# lab5.net
KiCad netlist of a schematic drawn in EAGLE
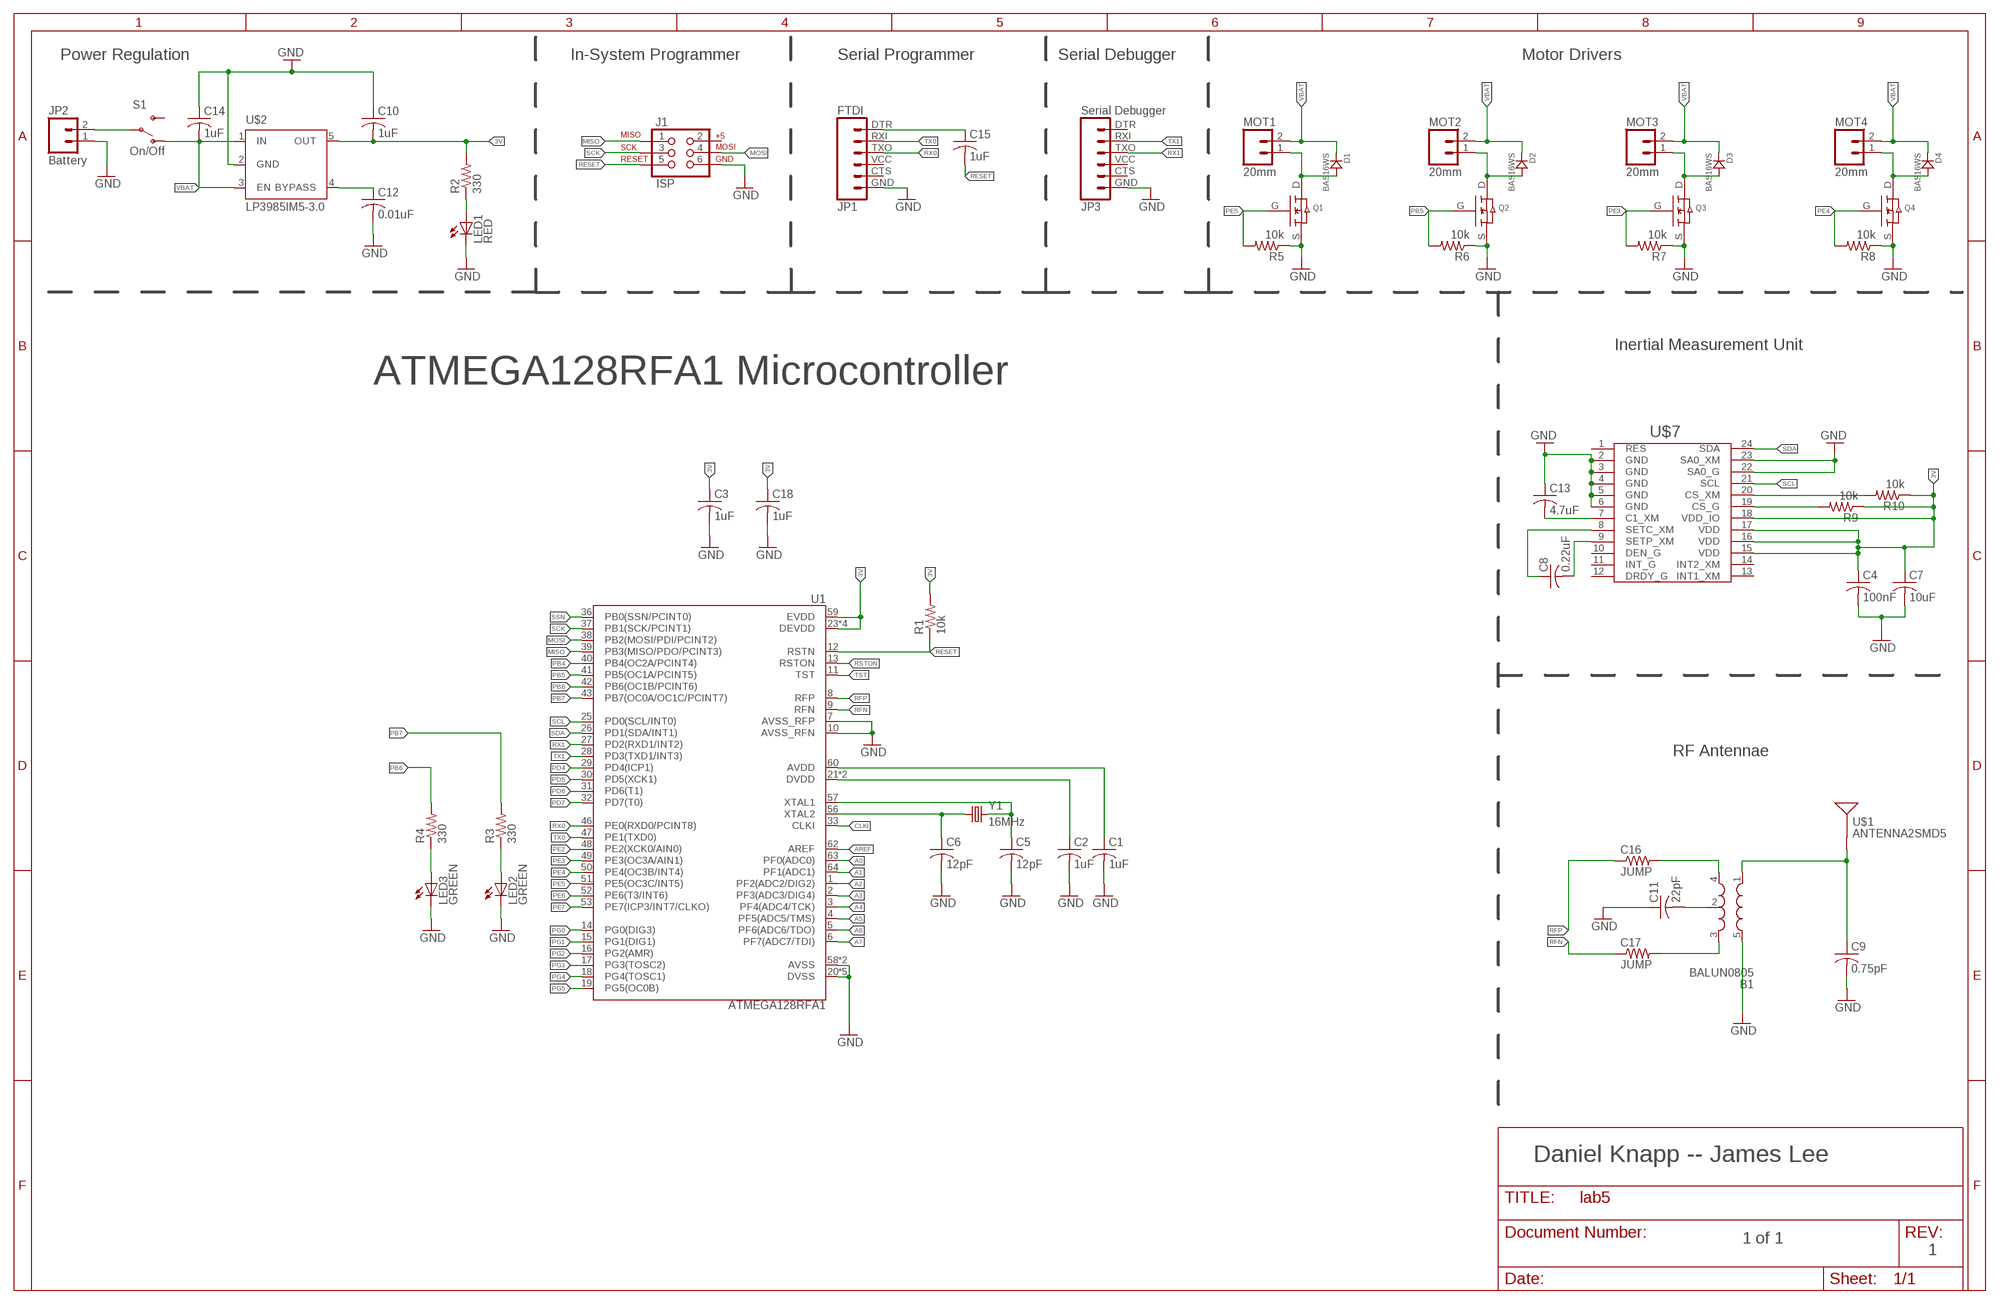
[diagram p0: schematic, sheet 1]

(export (version "E")
  (design (tool "Eeschema 10.0.6"))
  (components
    (comp (ref "B1")
      (value "BALUN0805")
      (footprint "eagle-import:BALUN")
      (libsource (lib "eagle-import") (part "BALUN0805"))
    )
    (comp (ref "C1")
      (value "1uF")
      (footprint "eagle-import:C0805")
      (libsource (lib "eagle-import") (part "C-USC0805"))
    )
    (comp (ref "C2")
      (value "1uF")
      (footprint "eagle-import:C0805")
      (libsource (lib "eagle-import") (part "C-USC0805"))
    )
    (comp (ref "C3")
      (value "1uF")
      (footprint "eagle-import:C0805")
      (libsource (lib "eagle-import") (part "C-USC0805"))
    )
    (comp (ref "C4")
      (value "100nF")
      (footprint "eagle-import:C0805")
      (libsource (lib "eagle-import") (part "C-USC0805"))
    )
    (comp (ref "C5")
      (value "12pF")
      (footprint "eagle-import:C0805")
      (libsource (lib "eagle-import") (part "C-USC0805"))
    )
    (comp (ref "C6")
      (value "12pF")
      (footprint "eagle-import:C0805")
      (libsource (lib "eagle-import") (part "C-USC0805"))
    )
    (comp (ref "C7")
      (value "10uF")
      (footprint "eagle-import:C0805")
      (libsource (lib "eagle-import") (part "C-USC0805"))
    )
    (comp (ref "C8")
      (value "0.22uF")
      (footprint "eagle-import:C0805")
      (libsource (lib "eagle-import") (part "C-USC0805"))
    )
    (comp (ref "C9")
      (value "0.75pF")
      (footprint "eagle-import:C0805")
      (libsource (lib "eagle-import") (part "C-USC0805"))
    )
    (comp (ref "C10")
      (value "1uF")
      (footprint "eagle-import:C0805")
      (libsource (lib "eagle-import") (part "C-USC0805"))
    )
    (comp (ref "C11")
      (value "22pF")
      (footprint "eagle-import:C0805")
      (libsource (lib "eagle-import") (part "C-USC0805"))
    )
    (comp (ref "C12")
      (value "0.01uF")
      (footprint "eagle-import:C0805")
      (libsource (lib "eagle-import") (part "C-USC0805"))
    )
    (comp (ref "C13")
      (value "4.7uF")
      (footprint "eagle-import:C0805")
      (libsource (lib "eagle-import") (part "C-USC0805"))
    )
    (comp (ref "C14")
      (value "1uF")
      (footprint "eagle-import:C0805")
      (libsource (lib "eagle-import") (part "C-USC0805"))
    )
    (comp (ref "C15")
      (value "1uF")
      (footprint "eagle-import:C0805")
      (libsource (lib "eagle-import") (part "C-USC0805"))
    )
    (comp (ref "C16")
      (value "JUMP")
      (footprint "eagle-import:R0805")
      (libsource (lib "eagle-import") (part "R-US_R0805"))
    )
    (comp (ref "C17")
      (value "JUMP")
      (footprint "eagle-import:R0805")
      (libsource (lib "eagle-import") (part "R-US_R0805"))
    )
    (comp (ref "C18")
      (value "1uF")
      (footprint "eagle-import:C0805")
      (libsource (lib "eagle-import") (part "C-USC0805"))
    )
    (comp (ref "D1")
      (value "BAS16WS")
      (footprint "eagle-import:BAS16WS")
      (fields (field (name "CREATOR") "Daniel Knapp"))
      (libsource (lib "eagle-import") (part "BAS16WS"))
    )
    (comp (ref "D2")
      (value "BAS16WS")
      (footprint "eagle-import:BAS16WS")
      (fields (field (name "CREATOR") "Daniel Knapp"))
      (libsource (lib "eagle-import") (part "BAS16WS"))
    )
    (comp (ref "D3")
      (value "BAS16WS")
      (footprint "eagle-import:BAS16WS")
      (fields (field (name "CREATOR") "Daniel Knapp"))
      (libsource (lib "eagle-import") (part "BAS16WS"))
    )
    (comp (ref "D4")
      (value "BAS16WS")
      (footprint "eagle-import:BAS16WS")
      (fields (field (name "CREATOR") "Daniel Knapp"))
      (libsource (lib "eagle-import") (part "BAS16WS"))
    )
    (comp (ref "J1")
      (value "ISP")
      (footprint "eagle-import:2X3-NS")
      (libsource (lib "eagle-import") (part "AVR_SPI_PRG_6NS"))
    )
    (comp (ref "JP1")
      (value "FTDI")
      (footprint "eagle-import:FTDI_BASIC")
      (libsource (lib "eagle-import") (part "FTDI_BASICPTH"))
    )
    (comp (ref "JP2")
      (value "Battery")
      (footprint "eagle-import:1X02")
      (libsource (lib "eagle-import") (part "M02PTH"))
    )
    (comp (ref "JP3")
      (value "Serial Debugger")
      (footprint "eagle-import:FTDI_BASIC")
      (libsource (lib "eagle-import") (part "FTDI_BASICPTH"))
    )
    (comp (ref "LED1")
      (value "RED")
      (footprint "eagle-import:CHIP-LED0805")
      (libsource (lib "eagle-import") (part "LEDCHIP-LED0805"))
    )
    (comp (ref "LED2")
      (value "GREEN")
      (footprint "eagle-import:CHIP-LED0805")
      (libsource (lib "eagle-import") (part "LEDCHIP-LED0805"))
    )
    (comp (ref "LED3")
      (value "GREEN")
      (footprint "eagle-import:CHIP-LED0805")
      (libsource (lib "eagle-import") (part "LEDCHIP-LED0805"))
    )
    (comp (ref "MOT1")
      (value "20mm")
      (footprint "eagle-import:1X02")
      (libsource (lib "eagle-import") (part "M02PTH"))
    )
    (comp (ref "MOT2")
      (value "20mm")
      (footprint "eagle-import:1X02")
      (libsource (lib "eagle-import") (part "M02PTH"))
    )
    (comp (ref "MOT3")
      (value "20mm")
      (footprint "eagle-import:1X02")
      (libsource (lib "eagle-import") (part "M02PTH"))
    )
    (comp (ref "MOT4")
      (value "20mm")
      (footprint "eagle-import:1X02")
      (libsource (lib "eagle-import") (part "M02PTH"))
    )
    (comp (ref "Q1")
      (value "SI2302CDS")
      (footprint "eagle-import:SI2302CDS")
      (fields (field (name "CREATOR") "Daniel Knapp"))
      (libsource (lib "eagle-import") (part "SI2302CDS"))
    )
    (comp (ref "Q2")
      (value "SI2302CDS")
      (footprint "eagle-import:SI2302CDS")
      (fields (field (name "CREATOR") "Daniel Knapp"))
      (libsource (lib "eagle-import") (part "SI2302CDS"))
    )
    (comp (ref "Q3")
      (value "SI2302CDS")
      (footprint "eagle-import:SI2302CDS")
      (fields (field (name "CREATOR") "Daniel Knapp"))
      (libsource (lib "eagle-import") (part "SI2302CDS"))
    )
    (comp (ref "Q4")
      (value "SI2302CDS")
      (footprint "eagle-import:SI2302CDS")
      (fields (field (name "CREATOR") "Daniel Knapp"))
      (libsource (lib "eagle-import") (part "SI2302CDS"))
    )
    (comp (ref "R1")
      (value "10k")
      (footprint "eagle-import:R0805")
      (libsource (lib "eagle-import") (part "R-US_R0805"))
    )
    (comp (ref "R2")
      (value "330")
      (footprint "eagle-import:R0805")
      (libsource (lib "eagle-import") (part "R-US_R0805"))
    )
    (comp (ref "R3")
      (value "330")
      (footprint "eagle-import:R0805")
      (libsource (lib "eagle-import") (part "R-US_R0805"))
    )
    (comp (ref "R4")
      (value "330")
      (footprint "eagle-import:R0805")
      (libsource (lib "eagle-import") (part "R-US_R0805"))
    )
    (comp (ref "R5")
      (value "10k")
      (footprint "eagle-import:R0805")
      (libsource (lib "eagle-import") (part "R-US_R0805"))
    )
    (comp (ref "R6")
      (value "10k")
      (footprint "eagle-import:R0805")
      (libsource (lib "eagle-import") (part "R-US_R0805"))
    )
    (comp (ref "R7")
      (value "10k")
      (footprint "eagle-import:R0805")
      (libsource (lib "eagle-import") (part "R-US_R0805"))
    )
    (comp (ref "R8")
      (value "10k")
      (footprint "eagle-import:R0805")
      (libsource (lib "eagle-import") (part "R-US_R0805"))
    )
    (comp (ref "R9")
      (value "10k")
      (footprint "eagle-import:R0805")
      (libsource (lib "eagle-import") (part "R-US_R0805"))
    )
    (comp (ref "R10")
      (value "10k")
      (footprint "eagle-import:R0805")
      (libsource (lib "eagle-import") (part "R-US_R0805"))
    )
    (comp (ref "S1")
      (value "On/Off")
      (footprint "eagle-import:SWITCH-SPDT")
      (libsource (lib "eagle-import") (part "SWITCH-SPDTPTH"))
    )
    (comp (ref "U$1")
      (value "ANTENNA2SMD5")
      (footprint "eagle-import:ANTENNA-CHIP5")
      (libsource (lib "eagle-import") (part "ANTENNA2SMD5"))
    )
    (comp (ref "U$2")
      (value "LP3985IM5-3.0")
      (footprint "eagle-import:SOT23-DBV")
      (libsource (lib "eagle-import") (part "LP3985IM5-3.0"))
    )
    (comp (ref "U$7")
      (value "LSM9DS0")
      (footprint "eagle-import:LSM9DS0")
      (fields (field (name "CREATOR") "Daniel Knapp"))
      (libsource (lib "eagle-import") (part "LSM9DS0"))
    )
    (comp (ref "U1")
      (value "ATMEGA128RFA1")
      (footprint "eagle-import:QFN-64")
      (libsource (lib "eagle-import") (part "ATMEGA128RFA1"))
    )
    (comp (ref "Y1")
      (value "16MHz")
      (footprint "eagle-import:CRYSTAL-SMD-5X3")
      (libsource (lib "eagle-import") (part "CRYSTAL5X3"))
    )
  )
  (nets
    (net (code "1") (name "3V") (class "Default")
      (node (ref "C10") (pin "2") (pinfunction "2_2") (pintype "passive"))
      (node (ref "C18") (pin "1") (pinfunction "1_1") (pintype "passive"))
      (node (ref "C3") (pin "1") (pinfunction "1_1") (pintype "passive"))
      (node (ref "C4") (pin "1") (pinfunction "1_1") (pintype "passive"))
      (node (ref "C7") (pin "1") (pinfunction "1_1") (pintype "passive"))
      (node (ref "R1") (pin "2") (pinfunction "2_2") (pintype "passive"))
      (node (ref "R10") (pin "1") (pinfunction "1_1") (pintype "passive"))
      (node (ref "R2") (pin "2") (pinfunction "2_2") (pintype "passive"))
      (node (ref "R9") (pin "1") (pinfunction "1_1") (pintype "passive"))
      (node (ref "U$2") (pin "5") (pinfunction "OUT_5") (pintype "passive"))
      (node (ref "U$7") (pin "15") (pinfunction "VDD_15") (pintype "bidirectional"))
      (node (ref "U$7") (pin "16") (pinfunction "VDD_16") (pintype "bidirectional"))
      (node (ref "U$7") (pin "17") (pinfunction "VDD_17") (pintype "bidirectional"))
      (node (ref "U$7") (pin "18") (pinfunction "VDD_IO_18") (pintype "bidirectional"))
      (node (ref "U1") (pin "23") (pinfunction "DEVDD_23") (pintype "bidirectional"))
      (node (ref "U1") (pin "34") (pinfunction "DEVDD_34") (pintype "bidirectional"))
      (node (ref "U1") (pin "44") (pinfunction "DEVDD_44") (pintype "bidirectional"))
      (node (ref "U1") (pin "54") (pinfunction "DEVDD_54") (pintype "bidirectional"))
      (node (ref "U1") (pin "59") (pinfunction "EVDD_59") (pintype "bidirectional"))
    )
    (net (code "2") (name "A0") (class "Default")
      (node (ref "U1") (pin "63") (pinfunction "PF0(ADC0)_63") (pintype "bidirectional"))
    )
    (net (code "3") (name "A1") (class "Default")
      (node (ref "U1") (pin "64") (pinfunction "PF1(ADC1)_64") (pintype "bidirectional"))
    )
    (net (code "4") (name "A2") (class "Default")
      (node (ref "U1") (pin "1") (pinfunction "PF2(ADC2/DIG2)_1") (pintype "bidirectional"))
    )
    (net (code "5") (name "A3") (class "Default")
      (node (ref "U1") (pin "2") (pinfunction "PF3(ADC3/DIG4)_2") (pintype "bidirectional"))
    )
    (net (code "6") (name "A4") (class "Default")
      (node (ref "U1") (pin "3") (pinfunction "PF4(ADC4/TCK)_3") (pintype "bidirectional"))
    )
    (net (code "7") (name "A5") (class "Default")
      (node (ref "U1") (pin "4") (pinfunction "PF5(ADC5/TMS)_4") (pintype "bidirectional"))
    )
    (net (code "8") (name "A6") (class "Default")
      (node (ref "U1") (pin "5") (pinfunction "PF6(ADC6/TDO)_5") (pintype "bidirectional"))
    )
    (net (code "9") (name "A7") (class "Default")
      (node (ref "U1") (pin "6") (pinfunction "PF7(ADC7/TDI)_6") (pintype "bidirectional"))
    )
    (net (code "10") (name "AREF") (class "Default")
      (node (ref "U1") (pin "62") (pinfunction "AREF_62") (pintype "bidirectional"))
    )
    (net (code "11") (name "CLKI") (class "Default")
      (node (ref "U1") (pin "33") (pinfunction "CLKI_33") (pintype "bidirectional"))
    )
    (net (code "12") (name "GND") (class "Default")
      (node (ref "B1") (pin "5") (pinfunction "GND_5") (pintype "bidirectional"))
      (node (ref "C1") (pin "2") (pinfunction "2_2") (pintype "passive"))
      (node (ref "C10") (pin "1") (pinfunction "1_1") (pintype "passive"))
      (node (ref "C11") (pin "1") (pinfunction "1_1") (pintype "passive"))
      (node (ref "C12") (pin "2") (pinfunction "2_2") (pintype "passive"))
      (node (ref "C13") (pin "1") (pinfunction "1_1") (pintype "passive"))
      (node (ref "C14") (pin "1") (pinfunction "1_1") (pintype "passive"))
      (node (ref "C18") (pin "2") (pinfunction "2_2") (pintype "passive"))
      (node (ref "C2") (pin "2") (pinfunction "2_2") (pintype "passive"))
      (node (ref "C3") (pin "2") (pinfunction "2_2") (pintype "passive"))
      (node (ref "C4") (pin "2") (pinfunction "2_2") (pintype "passive"))
      (node (ref "C5") (pin "2") (pinfunction "2_2") (pintype "passive"))
      (node (ref "C6") (pin "2") (pinfunction "2_2") (pintype "passive"))
      (node (ref "C7") (pin "2") (pinfunction "2_2") (pintype "passive"))
      (node (ref "C9") (pin "2") (pinfunction "2_2") (pintype "passive"))
      (node (ref "J1") (pin "6") (pinfunction "6_6") (pintype "passive"))
      (node (ref "JP1") (pin "GND") (pinfunction "6_GND") (pintype "passive"))
      (node (ref "JP2") (pin "1") (pinfunction "1_1") (pintype "passive"))
      (node (ref "JP3") (pin "GND") (pinfunction "6_GND") (pintype "passive"))
      (node (ref "LED1") (pin "C") (pinfunction "C_C") (pintype "passive"))
      (node (ref "LED2") (pin "C") (pinfunction "C_C") (pintype "passive"))
      (node (ref "LED3") (pin "C") (pinfunction "C_C") (pintype "passive"))
      (node (ref "Q1") (pin "S") (pinfunction "P$2_S") (pintype "passive"))
      (node (ref "Q2") (pin "S") (pinfunction "P$2_S") (pintype "passive"))
      (node (ref "Q3") (pin "S") (pinfunction "P$2_S") (pintype "passive"))
      (node (ref "Q4") (pin "S") (pinfunction "P$2_S") (pintype "passive"))
      (node (ref "R5") (pin "1") (pinfunction "1_1") (pintype "passive"))
      (node (ref "R6") (pin "1") (pinfunction "1_1") (pintype "passive"))
      (node (ref "R7") (pin "1") (pinfunction "1_1") (pintype "passive"))
      (node (ref "R8") (pin "1") (pinfunction "1_1") (pintype "passive"))
      (node (ref "U$2") (pin "2") (pinfunction "GND_2") (pintype "input"))
      (node (ref "U$7") (pin "2") (pinfunction "GND_2") (pintype "bidirectional"))
      (node (ref "U$7") (pin "22") (pinfunction "SA0_G_22") (pintype "bidirectional"))
      (node (ref "U$7") (pin "23") (pinfunction "SA0_XM_23") (pintype "bidirectional"))
      (node (ref "U$7") (pin "3") (pinfunction "GND_3") (pintype "bidirectional"))
      (node (ref "U$7") (pin "4") (pinfunction "GND_4") (pintype "bidirectional"))
      (node (ref "U$7") (pin "5") (pinfunction "GND_5") (pintype "bidirectional"))
      (node (ref "U$7") (pin "6") (pinfunction "GND_6") (pintype "bidirectional"))
      (node (ref "U1") (pin "10") (pinfunction "AVSS_RFN_10") (pintype "bidirectional"))
      (node (ref "U1") (pin "20") (pinfunction "DVSS_20") (pintype "bidirectional"))
      (node (ref "U1") (pin "24") (pinfunction "DVSS_24") (pintype "bidirectional"))
      (node (ref "U1") (pin "35") (pinfunction "DVSS_35") (pintype "bidirectional"))
      (node (ref "U1") (pin "45") (pinfunction "DVSS_45") (pintype "bidirectional"))
      (node (ref "U1") (pin "55") (pinfunction "DVSS_55") (pintype "bidirectional"))
      (node (ref "U1") (pin "58") (pinfunction "AVSS_58") (pintype "bidirectional"))
      (node (ref "U1") (pin "61") (pinfunction "AVSS_61") (pintype "bidirectional"))
      (node (ref "U1") (pin "7") (pinfunction "AVSS_RFP_7") (pintype "bidirectional"))
    )
    (net (code "13") (name "MISO") (class "Default")
      (node (ref "J1") (pin "1") (pinfunction "1_1") (pintype "passive"))
      (node (ref "U1") (pin "39") (pinfunction "PB3(MISO/PDO/PCINT3)_39") (pintype "bidirectional"))
    )
    (net (code "14") (name "MOSI") (class "Default")
      (node (ref "J1") (pin "4") (pinfunction "4_4") (pintype "passive"))
      (node (ref "U1") (pin "38") (pinfunction "PB2(MOSI/PDI/PCINT2)_38") (pintype "bidirectional"))
    )
    (net (code "15") (name "Net-(B1-GND-Pad2)") (class "Default")
      (node (ref "B1") (pin "2") (pinfunction "GND_2") (pintype "bidirectional"))
      (node (ref "C11") (pin "2") (pinfunction "2_2") (pintype "passive"))
    )
    (net (code "16") (name "Net-(B1-IN)") (class "Default")
      (node (ref "B1") (pin "1") (pinfunction "IN_1") (pintype "bidirectional"))
      (node (ref "C9") (pin "1") (pinfunction "1_1") (pintype "passive"))
      (node (ref "U$1") (pin "FEED") (pinfunction "SIGNAL_FEED") (pintype "bidirectional"))
    )
    (net (code "17") (name "Net-(B1-OUT1)") (class "Default")
      (node (ref "B1") (pin "4") (pinfunction "OUT1_4") (pintype "bidirectional"))
      (node (ref "C16") (pin "2") (pinfunction "2_2") (pintype "passive"))
    )
    (net (code "18") (name "Net-(B1-OUT2)") (class "Default")
      (node (ref "B1") (pin "3") (pinfunction "OUT2_3") (pintype "bidirectional"))
      (node (ref "C17") (pin "2") (pinfunction "2_2") (pintype "passive"))
    )
    (net (code "19") (name "Net-(C2-Pad1)") (class "Default")
      (node (ref "C2") (pin "1") (pinfunction "1_1") (pintype "passive"))
      (node (ref "U1") (pin "21") (pinfunction "DVDD_21") (pintype "bidirectional"))
      (node (ref "U1") (pin "22") (pinfunction "DVDD_22") (pintype "bidirectional"))
    )
    (net (code "20") (name "Net-(JP1-1)") (class "Default")
      (node (ref "C15") (pin "1") (pinfunction "1_1") (pintype "passive"))
      (node (ref "JP1") (pin "DTR") (pinfunction "1_DTR") (pintype "passive"))
    )
    (net (code "21") (name "Net-(LED1-PadA)") (class "Default")
      (node (ref "LED1") (pin "A") (pinfunction "A_A") (pintype "passive"))
      (node (ref "R2") (pin "1") (pinfunction "1_1") (pintype "passive"))
    )
    (net (code "22") (name "Net-(LED2-PadA)") (class "Default")
      (node (ref "LED2") (pin "A") (pinfunction "A_A") (pintype "passive"))
      (node (ref "R3") (pin "1") (pinfunction "1_1") (pintype "passive"))
    )
    (net (code "23") (name "Net-(LED3-PadA)") (class "Default")
      (node (ref "LED3") (pin "A") (pinfunction "A_A") (pintype "passive"))
      (node (ref "R4") (pin "1") (pinfunction "1_1") (pintype "passive"))
    )
    (net (code "24") (name "Net-(Q1-P$3)") (class "Default")
      (node (ref "D1") (pin "P$2") (pinfunction "P$2_P$2") (pintype "passive"))
      (node (ref "MOT1") (pin "1") (pinfunction "1_1") (pintype "passive"))
      (node (ref "Q1") (pin "D") (pinfunction "P$3_D") (pintype "passive"))
    )
    (net (code "25") (name "Net-(Q2-P$3)") (class "Default")
      (node (ref "D2") (pin "P$2") (pinfunction "P$2_P$2") (pintype "passive"))
      (node (ref "MOT2") (pin "1") (pinfunction "1_1") (pintype "passive"))
      (node (ref "Q2") (pin "D") (pinfunction "P$3_D") (pintype "passive"))
    )
    (net (code "26") (name "Net-(Q3-P$3)") (class "Default")
      (node (ref "D3") (pin "P$2") (pinfunction "P$2_P$2") (pintype "passive"))
      (node (ref "MOT3") (pin "1") (pinfunction "1_1") (pintype "passive"))
      (node (ref "Q3") (pin "D") (pinfunction "P$3_D") (pintype "passive"))
    )
    (net (code "27") (name "Net-(Q4-P$3)") (class "Default")
      (node (ref "D4") (pin "P$2") (pinfunction "P$2_P$2") (pintype "passive"))
      (node (ref "MOT4") (pin "1") (pinfunction "1_1") (pintype "passive"))
      (node (ref "Q4") (pin "D") (pinfunction "P$3_D") (pintype "passive"))
    )
    (net (code "28") (name "Net-(S1-P)") (class "Default")
      (node (ref "JP2") (pin "2") (pinfunction "2_2") (pintype "passive"))
      (node (ref "S1") (pin "2") (pinfunction "P_2") (pintype "passive"))
    )
    (net (code "29") (name "Net-(U$2-BYPASS)") (class "Default")
      (node (ref "C12") (pin "1") (pinfunction "1_1") (pintype "passive"))
      (node (ref "U$2") (pin "4") (pinfunction "BYPASS_4") (pintype "passive"))
    )
    (net (code "30") (name "Net-(U$7-C1_XM)") (class "Default")
      (node (ref "C13") (pin "2") (pinfunction "2_2") (pintype "passive"))
      (node (ref "U$7") (pin "7") (pinfunction "C1_XM_7") (pintype "bidirectional"))
    )
    (net (code "31") (name "Net-(U$7-CS_G)") (class "Default")
      (node (ref "R9") (pin "2") (pinfunction "2_2") (pintype "passive"))
      (node (ref "U$7") (pin "19") (pinfunction "CS_G_19") (pintype "bidirectional"))
    )
    (net (code "32") (name "Net-(U$7-CS_XM)") (class "Default")
      (node (ref "R10") (pin "2") (pinfunction "2_2") (pintype "passive"))
      (node (ref "U$7") (pin "20") (pinfunction "CS_XM_20") (pintype "bidirectional"))
    )
    (net (code "33") (name "Net-(U$7-SETC_XM)") (class "Default")
      (node (ref "C8") (pin "1") (pinfunction "1_1") (pintype "passive"))
      (node (ref "U$7") (pin "8") (pinfunction "SETC_XM_8") (pintype "bidirectional"))
    )
    (net (code "34") (name "Net-(U$7-SETP_XM)") (class "Default")
      (node (ref "C8") (pin "2") (pinfunction "2_2") (pintype "passive"))
      (node (ref "U$7") (pin "9") (pinfunction "SETP_XM_9") (pintype "bidirectional"))
    )
    (net (code "35") (name "Net-(U1-AVDD)") (class "Default")
      (node (ref "C1") (pin "1") (pinfunction "1_1") (pintype "passive"))
      (node (ref "U1") (pin "60") (pinfunction "AVDD_60") (pintype "bidirectional"))
    )
    (net (code "36") (name "Net-(U1-XTAL1)") (class "Default")
      (node (ref "C5") (pin "1") (pinfunction "1_1") (pintype "passive"))
      (node (ref "U1") (pin "57") (pinfunction "XTAL1_57") (pintype "bidirectional"))
      (node (ref "Y1") (pin "3") (pinfunction "2_3") (pintype "passive"))
    )
    (net (code "37") (name "Net-(U1-XTAL2)") (class "Default")
      (node (ref "C6") (pin "1") (pinfunction "1_1") (pintype "passive"))
      (node (ref "U1") (pin "56") (pinfunction "XTAL2_56") (pintype "bidirectional"))
      (node (ref "Y1") (pin "1") (pinfunction "1_1") (pintype "passive"))
    )
    (net (code "38") (name "PB4") (class "Default")
      (node (ref "U1") (pin "40") (pinfunction "PB4(OC2A/PCINT4)_40") (pintype "bidirectional"))
    )
    (net (code "39") (name "PB5") (class "Default")
      (node (ref "Q2") (pin "G") (pinfunction "P$1_G") (pintype "passive"))
      (node (ref "R6") (pin "2") (pinfunction "2_2") (pintype "passive"))
      (node (ref "U1") (pin "41") (pinfunction "PB5(OC1A/PCINT5)_41") (pintype "bidirectional"))
    )
    (net (code "40") (name "PB6") (class "Default")
      (node (ref "R4") (pin "2") (pinfunction "2_2") (pintype "passive"))
      (node (ref "U1") (pin "42") (pinfunction "PB6(OC1B/PCINT6)_42") (pintype "bidirectional"))
    )
    (net (code "41") (name "PB7") (class "Default")
      (node (ref "R3") (pin "2") (pinfunction "2_2") (pintype "passive"))
      (node (ref "U1") (pin "43") (pinfunction "PB7(OC0A/OC1C/PCINT7)_43") (pintype "bidirectional"))
    )
    (net (code "42") (name "PD4") (class "Default")
      (node (ref "U1") (pin "29") (pinfunction "PD4(ICP1)_29") (pintype "bidirectional"))
    )
    (net (code "43") (name "PD5") (class "Default")
      (node (ref "U1") (pin "30") (pinfunction "PD5(XCK1)_30") (pintype "bidirectional"))
    )
    (net (code "44") (name "PD6") (class "Default")
      (node (ref "U1") (pin "31") (pinfunction "PD6(T1)_31") (pintype "bidirectional"))
    )
    (net (code "45") (name "PD7") (class "Default")
      (node (ref "U1") (pin "32") (pinfunction "PD7(T0)_32") (pintype "bidirectional"))
    )
    (net (code "46") (name "PE2") (class "Default")
      (node (ref "U1") (pin "48") (pinfunction "PE2(XCK0/AIN0)_48") (pintype "bidirectional"))
    )
    (net (code "47") (name "PE3") (class "Default")
      (node (ref "Q3") (pin "G") (pinfunction "P$1_G") (pintype "passive"))
      (node (ref "R7") (pin "2") (pinfunction "2_2") (pintype "passive"))
      (node (ref "U1") (pin "49") (pinfunction "PE3(OC3A/AIN1)_49") (pintype "bidirectional"))
    )
    (net (code "48") (name "PE4") (class "Default")
      (node (ref "Q4") (pin "G") (pinfunction "P$1_G") (pintype "passive"))
      (node (ref "R8") (pin "2") (pinfunction "2_2") (pintype "passive"))
      (node (ref "U1") (pin "50") (pinfunction "PE4(OC3B/INT4)_50") (pintype "bidirectional"))
    )
    (net (code "49") (name "PE5") (class "Default")
      (node (ref "Q1") (pin "G") (pinfunction "P$1_G") (pintype "passive"))
      (node (ref "R5") (pin "2") (pinfunction "2_2") (pintype "passive"))
      (node (ref "U1") (pin "51") (pinfunction "PE5(OC3C/INT5)_51") (pintype "bidirectional"))
    )
    (net (code "50") (name "PE6") (class "Default")
      (node (ref "U1") (pin "52") (pinfunction "PE6(T3/INT6)_52") (pintype "bidirectional"))
    )
    (net (code "51") (name "PE7") (class "Default")
      (node (ref "U1") (pin "53") (pinfunction "PE7(ICP3/INT7/CLKO)_53") (pintype "bidirectional"))
    )
    (net (code "52") (name "PG0") (class "Default")
      (node (ref "U1") (pin "14") (pinfunction "PG0(DIG3)_14") (pintype "bidirectional"))
    )
    (net (code "53") (name "PG1") (class "Default")
      (node (ref "U1") (pin "15") (pinfunction "PG1(DIG1)_15") (pintype "bidirectional"))
    )
    (net (code "54") (name "PG2") (class "Default")
      (node (ref "U1") (pin "16") (pinfunction "PG2(AMR)_16") (pintype "bidirectional"))
    )
    (net (code "55") (name "PG3") (class "Default")
      (node (ref "U1") (pin "17") (pinfunction "PG3(TOSC2)_17") (pintype "bidirectional"))
    )
    (net (code "56") (name "PG4") (class "Default")
      (node (ref "U1") (pin "18") (pinfunction "PG4(TOSC1)_18") (pintype "bidirectional"))
    )
    (net (code "57") (name "PG5") (class "Default")
      (node (ref "U1") (pin "19") (pinfunction "PG5(OC0B)_19") (pintype "bidirectional"))
    )
    (net (code "58") (name "RESET") (class "Default")
      (node (ref "C15") (pin "2") (pinfunction "2_2") (pintype "passive"))
      (node (ref "J1") (pin "5") (pinfunction "5_5") (pintype "passive"))
      (node (ref "R1") (pin "1") (pinfunction "1_1") (pintype "passive"))
      (node (ref "U1") (pin "12") (pinfunction "RSTN_12") (pintype "bidirectional"))
    )
    (net (code "59") (name "RFN") (class "Default")
      (node (ref "C17") (pin "1") (pinfunction "1_1") (pintype "passive"))
      (node (ref "U1") (pin "9") (pinfunction "RFN_9") (pintype "bidirectional"))
    )
    (net (code "60") (name "RFP") (class "Default")
      (node (ref "C16") (pin "1") (pinfunction "1_1") (pintype "passive"))
      (node (ref "U1") (pin "8") (pinfunction "RFP_8") (pintype "bidirectional"))
    )
    (net (code "61") (name "RSTON") (class "Default")
      (node (ref "U1") (pin "13") (pinfunction "RSTON_13") (pintype "bidirectional"))
    )
    (net (code "62") (name "RX0") (class "Default")
      (node (ref "JP1") (pin "TXO") (pinfunction "3_TXO") (pintype "passive"))
      (node (ref "U1") (pin "46") (pinfunction "PE0(RXD0/PCINT8)_46") (pintype "bidirectional"))
    )
    (net (code "63") (name "RX1") (class "Default")
      (node (ref "JP3") (pin "TXO") (pinfunction "3_TXO") (pintype "passive"))
      (node (ref "U1") (pin "27") (pinfunction "PD2(RXD1/INT2)_27") (pintype "bidirectional"))
    )
    (net (code "64") (name "SCK") (class "Default")
      (node (ref "J1") (pin "3") (pinfunction "3_3") (pintype "passive"))
      (node (ref "U1") (pin "37") (pinfunction "PB1(SCK/PCINT1)_37") (pintype "bidirectional"))
    )
    (net (code "65") (name "SCL") (class "Default")
      (node (ref "U$7") (pin "21") (pinfunction "SCL_21") (pintype "bidirectional"))
      (node (ref "U1") (pin "25") (pinfunction "PD0(SCL/INT0)_25") (pintype "bidirectional"))
    )
    (net (code "66") (name "SDA") (class "Default")
      (node (ref "U$7") (pin "24") (pinfunction "SDA_24") (pintype "bidirectional"))
      (node (ref "U1") (pin "26") (pinfunction "PD1(SDA/INT1)_26") (pintype "bidirectional"))
    )
    (net (code "67") (name "SSN") (class "Default")
      (node (ref "U1") (pin "36") (pinfunction "PB0(SSN/PCINT0)_36") (pintype "bidirectional"))
    )
    (net (code "68") (name "TST") (class "Default")
      (node (ref "U1") (pin "11") (pinfunction "TST_11") (pintype "bidirectional"))
    )
    (net (code "69") (name "TX0") (class "Default")
      (node (ref "JP1") (pin "RXI") (pinfunction "2_RXI") (pintype "passive"))
      (node (ref "U1") (pin "47") (pinfunction "PE1(TXD0)_47") (pintype "bidirectional"))
    )
    (net (code "70") (name "TX1") (class "Default")
      (node (ref "JP3") (pin "RXI") (pinfunction "2_RXI") (pintype "passive"))
      (node (ref "U1") (pin "28") (pinfunction "PD3(TXD1/INT3)_28") (pintype "bidirectional"))
    )
    (net (code "71") (name "VBAT") (class "Default")
      (node (ref "C14") (pin "2") (pinfunction "2_2") (pintype "passive"))
      (node (ref "D1") (pin "P$1") (pinfunction "P$1_P$1") (pintype "passive"))
      (node (ref "D2") (pin "P$1") (pinfunction "P$1_P$1") (pintype "passive"))
      (node (ref "D3") (pin "P$1") (pinfunction "P$1_P$1") (pintype "passive"))
      (node (ref "D4") (pin "P$1") (pinfunction "P$1_P$1") (pintype "passive"))
      (node (ref "MOT1") (pin "2") (pinfunction "2_2") (pintype "passive"))
      (node (ref "MOT2") (pin "2") (pinfunction "2_2") (pintype "passive"))
      (node (ref "MOT3") (pin "2") (pinfunction "2_2") (pintype "passive"))
      (node (ref "MOT4") (pin "2") (pinfunction "2_2") (pintype "passive"))
      (node (ref "S1") (pin "1") (pinfunction "O_1") (pintype "passive"))
      (node (ref "U$2") (pin "1") (pinfunction "IN_1") (pintype "input"))
      (node (ref "U$2") (pin "3") (pinfunction "EN_3") (pintype "input"))
    )
    (net (code "72") (name "unconnected-(J1-Pad2)") (class "Default")
      (node (ref "J1") (pin "2") (pinfunction "2_2") (pintype "passive"))
    )
    (net (code "73") (name "unconnected-(JP1-4-PadVCC)") (class "Default")
      (node (ref "JP1") (pin "VCC") (pinfunction "4_VCC") (pintype "passive"))
    )
    (net (code "74") (name "unconnected-(JP1-5-PadCTS)") (class "Default")
      (node (ref "JP1") (pin "CTS") (pinfunction "5_CTS") (pintype "passive"))
    )
    (net (code "75") (name "unconnected-(JP3-1-PadDTR)") (class "Default")
      (node (ref "JP3") (pin "DTR") (pinfunction "1_DTR") (pintype "passive"))
    )
    (net (code "76") (name "unconnected-(JP3-4-PadVCC)") (class "Default")
      (node (ref "JP3") (pin "VCC") (pinfunction "4_VCC") (pintype "passive"))
    )
    (net (code "77") (name "unconnected-(JP3-5-PadCTS)") (class "Default")
      (node (ref "JP3") (pin "CTS") (pinfunction "5_CTS") (pintype "passive"))
    )
    (net (code "78") (name "unconnected-(S1-S-Pad3)") (class "Default")
      (node (ref "S1") (pin "3") (pinfunction "S_3") (pintype "passive"))
    )
    (net (code "79") (name "unconnected-(U$7-DEN_G-Pad10)") (class "Default")
      (node (ref "U$7") (pin "10") (pinfunction "DEN_G_10") (pintype "bidirectional"))
    )
    (net (code "80") (name "unconnected-(U$7-DRDY_G-Pad12)") (class "Default")
      (node (ref "U$7") (pin "12") (pinfunction "DRDY_G_12") (pintype "bidirectional"))
    )
    (net (code "81") (name "unconnected-(U$7-INT1_XM-Pad13)") (class "Default")
      (node (ref "U$7") (pin "13") (pinfunction "INT1_XM_13") (pintype "bidirectional"))
    )
    (net (code "82") (name "unconnected-(U$7-INT2_XM-Pad14)") (class "Default")
      (node (ref "U$7") (pin "14") (pinfunction "INT2_XM_14") (pintype "bidirectional"))
    )
    (net (code "83") (name "unconnected-(U$7-INT_G-Pad11)") (class "Default")
      (node (ref "U$7") (pin "11") (pinfunction "INT_G_11") (pintype "bidirectional"))
    )
    (net (code "84") (name "unconnected-(U$7-RES-Pad1)") (class "Default")
      (node (ref "U$7") (pin "1") (pinfunction "RES_1") (pintype "bidirectional"))
    )
  )
)
